# MCU.net
KiCad netlist of a schematic drawn in Altium Designer
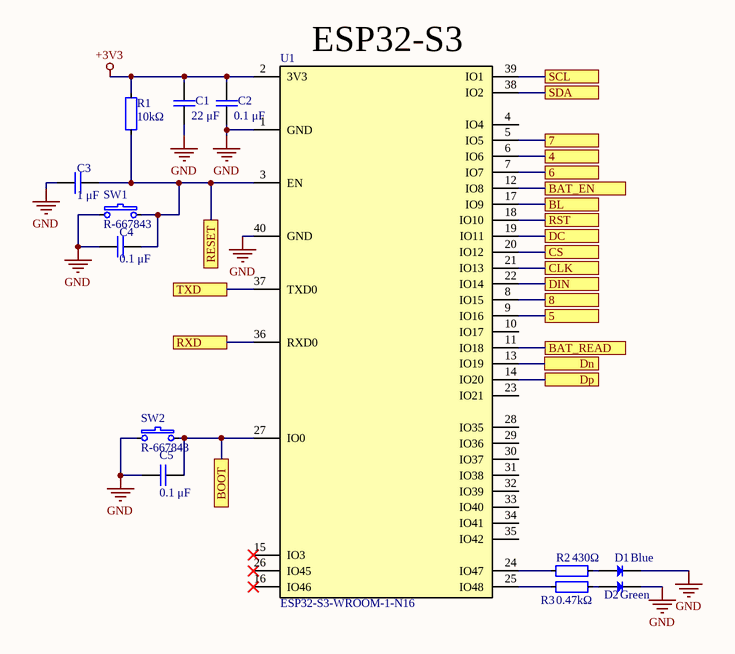
[diagram p0: MCU.SchDoc]

(export (version "E")
  (design (tool "Eeschema 10.0.6"))
  (components
    (comp (ref "C1")
      (value "22 μF")
      (footprint "Capacitor 0603")
      (description "Capacitor 22 μF")
      (fields
        (field (name "MANUFACTURER") "Murata Electronics")
        (field (name "MANUFACTURER PART NUMBER") "GRM188R60G226MEA0D")
      )
      (libsource (lib "Schlib1") (part "22 μF 0603"))
    )
    (comp (ref "C2")
      (value "0.1 μF")
      (footprint "Capacitor 0603")
      (description "Capacitor 0.1 μF")
      (fields
        (field (name "MANUFACTURER") "Samsung Electro-Mechanics")
        (field (name "MANUFACTURER PART NUMBER") "CL10B104KB8NNWC")
      )
      (libsource (lib "Schlib1") (part "0.1 μF 0603"))
    )
    (comp (ref "C3")
      (value "1 μF")
      (footprint "Capacitor 0603")
      (description "Capacitor 1 μF")
      (fields
        (field (name "MANUFACTURER") "Samsung Electro-Mechanics")
        (field (name "MANUFACTURER PART NUMBER") "CL10A105KA8NNNC")
      )
      (libsource (lib "Schlib1") (part "1 μF 0603"))
    )
    (comp (ref "C4")
      (value "0.1 μF")
      (footprint "Capacitor 0603")
      (description "Capacitor 0.1 μF")
      (fields
        (field (name "MANUFACTURER") "Samsung Electro-Mechanics")
        (field (name "MANUFACTURER PART NUMBER") "CL10B104KB8NNWC")
      )
      (libsource (lib "Schlib1") (part "0.1 μF 0603"))
    )
    (comp (ref "C5")
      (value "0.1 μF")
      (footprint "Capacitor 0603")
      (description "Capacitor 0.1 μF")
      (fields
        (field (name "MANUFACTURER") "Samsung Electro-Mechanics")
        (field (name "MANUFACTURER PART NUMBER") "CL10B104KB8NNWC")
      )
      (libsource (lib "Schlib1") (part "0.1 μF 0603"))
    )
    (comp (ref "D1")
      (value "Blue")
      (footprint "LED 0603")
      (description "Diode Blue")
      (fields
        (field (name "MANUFACTURER") "Lite-On Inc.")
        (field (name "MANUFACTURER PART NUMBER") "LTST-C193TBKT-5A")
      )
      (libsource (lib "Schlib1") (part "D.Blue"))
    )
    (comp (ref "D2")
      (value "Green")
      (footprint "LED 0603")
      (description "Diode Green")
      (fields
        (field (name "MANUFACTURER") "Lumex Opto/Components Inc.")
        (field (name "MANUFACTURER PART NUMBER") "SML-LXFT0603GC-TR")
      )
      (libsource (lib "Schlib1") (part "D.Green"))
    )
    (comp (ref "R1")
      (value "10kΩ")
      (footprint "Resistor 0603")
      (description "Resistor 10000 Ω")
      (fields
        (field (name "MANUFACTURER") "Stackpole Electronics Inc")
        (field (name "MANUFACTURER PART NUMBER") "RMCF0603FT10K0")
      )
      (libsource (lib "Schlib1") (part "10 kΩ 0603"))
    )
    (comp (ref "R2")
      (value "430Ω")
      (footprint "Resistor 0603")
      (description "Resistor 430 Ω")
      (fields
        (field (name "MANUFACTURER") "Stackpole Electronics Inc")
        (field (name "MANUFACTURER PART NUMBER") "RMCF0603JT430R")
      )
      (libsource (lib "SchLib") (part "430 Ω 0603"))
    )
    (comp (ref "R3")
      (value "0.47kΩ")
      (footprint "Resistor 0603")
      (description "Resistor 470 Ω")
      (fields
        (field (name "MANUFACTURER") "Stackpole Electronics Inc")
        (field (name "MANUFACTURER PART NUMBER") "RMCF0603FT470R")
      )
      (libsource (lib "SchLib") (part "0.47 kΩ 0603"))
    )
    (comp (ref "SW1")
      (value "R-667843")
      (footprint "R-667843")
      (description "SWITCH TACTILE SPST-NO 0.05A 12V")
      (fields (field (name "MANUFACTURER") "Mitsumi Electric Company Ltd"))
      (libsource (lib "Schlib1") (part "R-667843"))
    )
    (comp (ref "SW2")
      (value "R-667843")
      (footprint "R-667843")
      (description "SWITCH TACTILE SPST-NO 0.05A 12V")
      (fields (field (name "MANUFACTURER") "Mitsumi Electric Company Ltd"))
      (libsource (lib "Schlib1") (part "R-667843"))
    )
    (comp (ref "U1")
      (value "ESP32-S3-WROOM-1-N16")
      (footprint "ESP32-C3-WROOM-1")
      (description "RF TXRX MODULE BT PCB TRACE SMD")
      (fields (field (name "MANUFACTURER") "Espressif Systems"))
      (libsource (lib "SchLib") (part "ESP32-S3-WROOM-1-N16"))
    )
  )
  (nets
    (net (code "1") (name "+3V3") (class "Default")
      (node (ref "C1") (pin "B") (pinfunction "B_B") (pintype "passive"))
      (node (ref "C2") (pin "B") (pinfunction "B_B") (pintype "passive"))
      (node (ref "R1") (pin "A") (pinfunction "A_A") (pintype "passive"))
      (node (ref "U1") (pin "2") (pinfunction "3V3_2") (pintype "passive"))
    )
    (net (code "2") (name "/4") (class "Default")
      (node (ref "U1") (pin "6") (pinfunction "IO6_6") (pintype "passive"))
    )
    (net (code "3") (name "/5") (class "Default")
      (node (ref "U1") (pin "9") (pinfunction "IO16_9") (pintype "passive"))
    )
    (net (code "4") (name "/6") (class "Default")
      (node (ref "U1") (pin "7") (pinfunction "IO7_7") (pintype "passive"))
    )
    (net (code "5") (name "/7") (class "Default")
      (node (ref "U1") (pin "5") (pinfunction "IO5_5") (pintype "passive"))
    )
    (net (code "6") (name "/8") (class "Default")
      (node (ref "U1") (pin "8") (pinfunction "IO15_8") (pintype "passive"))
    )
    (net (code "7") (name "/BAT_EN") (class "Default")
      (node (ref "U1") (pin "12") (pinfunction "IO8_12") (pintype "passive"))
    )
    (net (code "8") (name "/BAT_READ") (class "Default")
      (node (ref "U1") (pin "11") (pinfunction "IO18_11") (pintype "passive"))
    )
    (net (code "9") (name "/BL") (class "Default")
      (node (ref "U1") (pin "17") (pinfunction "IO9_17") (pintype "passive"))
    )
    (net (code "10") (name "/BOOT") (class "Default")
      (node (ref "C5") (pin "A") (pinfunction "A_A") (pintype "passive"))
      (node (ref "SW2") (pin "A") (pinfunction "A_A") (pintype "passive"))
      (node (ref "U1") (pin "27") (pinfunction "IO0_27") (pintype "passive"))
    )
    (net (code "11") (name "/CLK") (class "Default")
      (node (ref "U1") (pin "21") (pinfunction "IO13_21") (pintype "passive"))
    )
    (net (code "12") (name "/CS") (class "Default")
      (node (ref "U1") (pin "20") (pinfunction "IO12_20") (pintype "passive"))
    )
    (net (code "13") (name "/DC") (class "Default")
      (node (ref "U1") (pin "19") (pinfunction "IO11_19") (pintype "passive"))
    )
    (net (code "14") (name "/DIN") (class "Default")
      (node (ref "U1") (pin "22") (pinfunction "IO14_22") (pintype "passive"))
    )
    (net (code "15") (name "/Dn") (class "Default")
      (node (ref "U1") (pin "13") (pinfunction "IO19_13") (pintype "passive"))
    )
    (net (code "16") (name "/Dp") (class "Default")
      (node (ref "U1") (pin "14") (pinfunction "IO20_14") (pintype "passive"))
    )
    (net (code "17") (name "/RESET") (class "Default")
      (node (ref "C3") (pin "B") (pinfunction "B_B") (pintype "passive"))
      (node (ref "C4") (pin "B") (pinfunction "B_B") (pintype "passive"))
      (node (ref "R1") (pin "B") (pinfunction "B_B") (pintype "passive"))
      (node (ref "SW1") (pin "B") (pinfunction "B_B") (pintype "passive"))
      (node (ref "U1") (pin "3") (pinfunction "EN_3") (pintype "passive"))
    )
    (net (code "18") (name "/RST") (class "Default")
      (node (ref "U1") (pin "18") (pinfunction "IO10_18") (pintype "passive"))
    )
    (net (code "19") (name "/RXD") (class "Default")
      (node (ref "U1") (pin "36") (pinfunction "RXD0_36") (pintype "passive"))
    )
    (net (code "20") (name "/SCL") (class "Default")
      (node (ref "U1") (pin "39") (pinfunction "IO1_39") (pintype "passive"))
    )
    (net (code "21") (name "/SDA") (class "Default")
      (node (ref "U1") (pin "38") (pinfunction "IO2_38") (pintype "passive"))
    )
    (net (code "22") (name "/TXD") (class "Default")
      (node (ref "U1") (pin "37") (pinfunction "TXD0_37") (pintype "passive"))
    )
    (net (code "23") (name "GND") (class "Default")
      (node (ref "C1") (pin "A") (pinfunction "A_A") (pintype "passive"))
      (node (ref "C2") (pin "A") (pinfunction "A_A") (pintype "passive"))
      (node (ref "C3") (pin "A") (pinfunction "A_A") (pintype "passive"))
      (node (ref "C4") (pin "A") (pinfunction "A_A") (pintype "passive"))
      (node (ref "C5") (pin "B") (pinfunction "B_B") (pintype "passive"))
      (node (ref "D1") (pin "B") (pinfunction "B_B") (pintype "passive"))
      (node (ref "D2") (pin "B") (pinfunction "B_B") (pintype "passive"))
      (node (ref "SW1") (pin "A") (pinfunction "A_A") (pintype "passive"))
      (node (ref "SW2") (pin "B") (pinfunction "B_B") (pintype "passive"))
      (node (ref "U1") (pin "1") (pinfunction "GND_1") (pintype "passive"))
      (node (ref "U1") (pin "40") (pinfunction "GND_40") (pintype "passive"))
    )
    (net (code "24") (name "Net-(D1-PadA)") (class "Default")
      (node (ref "D1") (pin "A") (pinfunction "A_A") (pintype "passive"))
      (node (ref "R2") (pin "B") (pinfunction "B_B") (pintype "passive"))
    )
    (net (code "25") (name "Net-(D2-PadA)") (class "Default")
      (node (ref "D2") (pin "A") (pinfunction "A_A") (pintype "passive"))
      (node (ref "R3") (pin "B") (pinfunction "B_B") (pintype "passive"))
    )
    (net (code "26") (name "Net-(U1-IO47)") (class "Default")
      (node (ref "R2") (pin "A") (pinfunction "A_A") (pintype "passive"))
      (node (ref "U1") (pin "24") (pinfunction "IO47_24") (pintype "passive"))
    )
    (net (code "27") (name "Net-(U1-IO48)") (class "Default")
      (node (ref "R3") (pin "A") (pinfunction "A_A") (pintype "passive"))
      (node (ref "U1") (pin "25") (pinfunction "IO48_25") (pintype "passive"))
    )
    (net (code "28") (name "unconnected-(U1-IO3-Pad15)") (class "Default")
      (node (ref "U1") (pin "15") (pinfunction "IO3_15") (pintype "passive+no_connect"))
    )
    (net (code "29") (name "unconnected-(U1-IO4-Pad4)") (class "Default")
      (node (ref "U1") (pin "4") (pinfunction "IO4_4") (pintype "passive"))
    )
    (net (code "30") (name "unconnected-(U1-IO17-Pad10)") (class "Default")
      (node (ref "U1") (pin "10") (pinfunction "IO17_10") (pintype "passive"))
    )
    (net (code "31") (name "unconnected-(U1-IO21-Pad23)") (class "Default")
      (node (ref "U1") (pin "23") (pinfunction "IO21_23") (pintype "passive"))
    )
    (net (code "32") (name "unconnected-(U1-IO35-Pad28)") (class "Default")
      (node (ref "U1") (pin "28") (pinfunction "IO35_28") (pintype "passive"))
    )
    (net (code "33") (name "unconnected-(U1-IO36-Pad29)") (class "Default")
      (node (ref "U1") (pin "29") (pinfunction "IO36_29") (pintype "passive"))
    )
    (net (code "34") (name "unconnected-(U1-IO37-Pad30)") (class "Default")
      (node (ref "U1") (pin "30") (pinfunction "IO37_30") (pintype "passive"))
    )
    (net (code "35") (name "unconnected-(U1-IO38-Pad31)") (class "Default")
      (node (ref "U1") (pin "31") (pinfunction "IO38_31") (pintype "passive"))
    )
    (net (code "36") (name "unconnected-(U1-IO39-Pad32)") (class "Default")
      (node (ref "U1") (pin "32") (pinfunction "IO39_32") (pintype "passive"))
    )
    (net (code "37") (name "unconnected-(U1-IO40-Pad33)") (class "Default")
      (node (ref "U1") (pin "33") (pinfunction "IO40_33") (pintype "passive"))
    )
    (net (code "38") (name "unconnected-(U1-IO41-Pad34)") (class "Default")
      (node (ref "U1") (pin "34") (pinfunction "IO41_34") (pintype "passive"))
    )
    (net (code "39") (name "unconnected-(U1-IO42-Pad35)") (class "Default")
      (node (ref "U1") (pin "35") (pinfunction "IO42_35") (pintype "passive"))
    )
    (net (code "40") (name "unconnected-(U1-IO45-Pad26)") (class "Default")
      (node (ref "U1") (pin "26") (pinfunction "IO45_26") (pintype "passive+no_connect"))
    )
    (net (code "41") (name "unconnected-(U1-IO46-Pad16)") (class "Default")
      (node (ref "U1") (pin "16") (pinfunction "IO46_16") (pintype "passive+no_connect"))
    )
  )
)
